# Power.net
KiCad netlist of a schematic drawn in Altium Designer
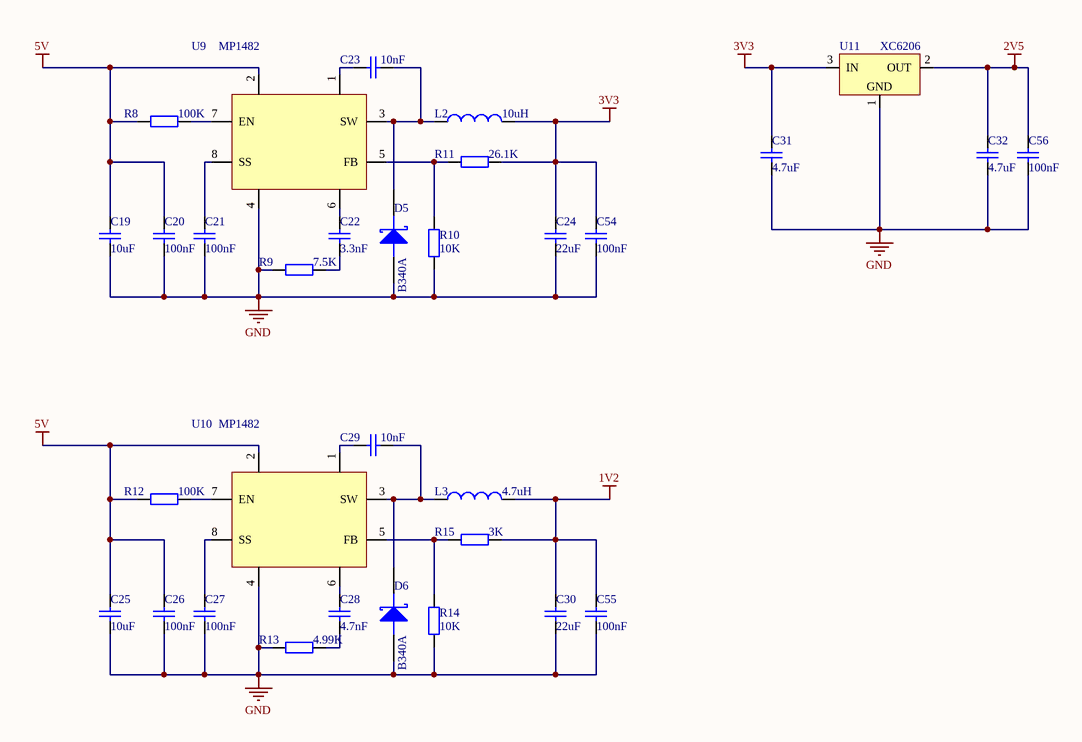
[diagram p0: Power.SchDoc]

(export (version "E")
  (design (tool "Eeschema 10.0.6"))
  (components
    (comp (ref "C19")
      (value "10uF")
      (footprint "C1206")
      (description "Capacitor")
      (fields (field (name "PUBLISHER") "Altium Limited"))
      (libsource (lib "Miscellaneous Devices") (part "Cap"))
    )
    (comp (ref "C20")
      (value "100nF")
      (footprint "C0603")
      (description "Capacitor")
      (fields (field (name "PUBLISHER") "Altium Limited"))
      (libsource (lib "Miscellaneous Devices") (part "Cap"))
    )
    (comp (ref "C21")
      (value "100nF")
      (footprint "C0603")
      (description "Capacitor")
      (fields (field (name "PUBLISHER") "Altium Limited"))
      (libsource (lib "Miscellaneous Devices") (part "Cap"))
    )
    (comp (ref "C22")
      (value "3.3nF")
      (footprint "C0603")
      (description "Capacitor")
      (fields (field (name "PUBLISHER") "Altium Limited"))
      (libsource (lib "Miscellaneous Devices") (part "Cap"))
    )
    (comp (ref "C23")
      (value "10nF")
      (footprint "C0603")
      (description "Capacitor")
      (fields (field (name "PUBLISHER") "Altium Limited"))
      (libsource (lib "Miscellaneous Devices") (part "Cap"))
    )
    (comp (ref "C24")
      (value "22uF")
      (footprint "C1206")
      (description "Capacitor")
      (fields (field (name "PUBLISHER") "Altium Limited"))
      (libsource (lib "Miscellaneous Devices") (part "Cap"))
    )
    (comp (ref "C25")
      (value "10uF")
      (footprint "C1206")
      (description "Capacitor")
      (fields (field (name "PUBLISHER") "Altium Limited"))
      (libsource (lib "Miscellaneous Devices") (part "Cap"))
    )
    (comp (ref "C26")
      (value "100nF")
      (footprint "C0603")
      (description "Capacitor")
      (fields (field (name "PUBLISHER") "Altium Limited"))
      (libsource (lib "Miscellaneous Devices") (part "Cap"))
    )
    (comp (ref "C27")
      (value "100nF")
      (footprint "C0603")
      (description "Capacitor")
      (fields (field (name "PUBLISHER") "Altium Limited"))
      (libsource (lib "Miscellaneous Devices") (part "Cap"))
    )
    (comp (ref "C28")
      (value "4.7nF")
      (footprint "C0603")
      (description "Capacitor")
      (fields (field (name "PUBLISHER") "Altium Limited"))
      (libsource (lib "Miscellaneous Devices") (part "Cap"))
    )
    (comp (ref "C29")
      (value "10nF")
      (footprint "C0603")
      (description "Capacitor")
      (fields (field (name "PUBLISHER") "Altium Limited"))
      (libsource (lib "Miscellaneous Devices") (part "Cap"))
    )
    (comp (ref "C30")
      (value "22uF")
      (footprint "C1206")
      (description "Capacitor")
      (fields (field (name "PUBLISHER") "Altium Limited"))
      (libsource (lib "Miscellaneous Devices") (part "Cap"))
    )
    (comp (ref "C31")
      (value "4.7uF")
      (footprint "C0603")
      (description "Capacitor")
      (fields (field (name "PUBLISHER") "Altium Limited"))
      (libsource (lib "Miscellaneous Devices") (part "Cap"))
    )
    (comp (ref "C32")
      (value "4.7uF")
      (footprint "C0603")
      (description "Capacitor")
      (fields (field (name "PUBLISHER") "Altium Limited"))
      (libsource (lib "Miscellaneous Devices") (part "Cap"))
    )
    (comp (ref "C54")
      (value "100nF")
      (footprint "C0603")
      (description "Capacitor")
      (fields (field (name "PUBLISHER") "Altium Limited"))
      (libsource (lib "Miscellaneous Devices") (part "Cap"))
    )
    (comp (ref "C55")
      (value "100nF")
      (footprint "C0603")
      (description "Capacitor")
      (fields (field (name "PUBLISHER") "Altium Limited"))
      (libsource (lib "Miscellaneous Devices") (part "Cap"))
    )
    (comp (ref "C56")
      (value "100nF")
      (footprint "C0603")
      (description "Capacitor")
      (fields (field (name "PUBLISHER") "Altium Limited"))
      (libsource (lib "Miscellaneous Devices") (part "Cap"))
    )
    (comp (ref "D5")
      (value "B340A")
      (footprint "SMA")
      (description "Schottky Diode")
      (libsource (lib "JL_SCH") (part "DIODE SCHOTTKY"))
    )
    (comp (ref "D6")
      (value "B340A")
      (footprint "SMA")
      (description "Schottky Diode")
      (libsource (lib "JL_SCH") (part "DIODE SCHOTTKY"))
    )
    (comp (ref "L2")
      (value "10uH")
      (footprint "CDRH5D28")
      (description "Inductor")
      (fields (field (name "PUBLISHER") "Altium Limited"))
      (libsource (lib "Miscellaneous Devices") (part "Inductor"))
    )
    (comp (ref "L3")
      (value "4.7uH")
      (footprint "CDRH5D28")
      (description "Inductor")
      (fields (field (name "PUBLISHER") "Altium Limited"))
      (libsource (lib "Miscellaneous Devices") (part "Inductor"))
    )
    (comp (ref "R8")
      (value "100K")
      (footprint "R0603")
      (description "Resistor")
      (fields (field (name "PUBLISHER") "Altium Limited"))
      (libsource (lib "Miscellaneous Devices") (part "Res2"))
    )
    (comp (ref "R9")
      (value "7.5K")
      (footprint "R0603")
      (description "Resistor")
      (fields (field (name "PUBLISHER") "Altium Limited"))
      (libsource (lib "Miscellaneous Devices") (part "Res2"))
    )
    (comp (ref "R10")
      (value "10K")
      (footprint "R0603")
      (description "Resistor")
      (fields (field (name "PUBLISHER") "Altium Limited"))
      (libsource (lib "") (part "Res2_1"))
    )
    (comp (ref "R11")
      (value "26.1K")
      (footprint "R0603")
      (description "Resistor")
      (fields (field (name "PUBLISHER") "Altium Limited"))
      (libsource (lib "Miscellaneous Devices") (part "Res2"))
    )
    (comp (ref "R12")
      (value "100K")
      (footprint "R0603")
      (description "Resistor")
      (fields (field (name "PUBLISHER") "Altium Limited"))
      (libsource (lib "Miscellaneous Devices") (part "Res2"))
    )
    (comp (ref "R13")
      (value "4.99K")
      (footprint "R0603")
      (description "Resistor")
      (fields (field (name "PUBLISHER") "Altium Limited"))
      (libsource (lib "Miscellaneous Devices") (part "Res2"))
    )
    (comp (ref "R14")
      (value "10K")
      (footprint "R0603")
      (description "Resistor")
      (fields (field (name "PUBLISHER") "Altium Limited"))
      (libsource (lib "") (part "Res2_1"))
    )
    (comp (ref "R15")
      (value "3K")
      (footprint "R0603")
      (description "Resistor")
      (fields (field (name "PUBLISHER") "Altium Limited"))
      (libsource (lib "Miscellaneous Devices") (part "Res2"))
    )
    (comp (ref "U9") (value "MP1482") (footprint "SOIC-8") (libsource (lib "ssmaster_1") (part "MP1482")))
    (comp (ref "U10") (value "MP1482") (footprint "SOIC-8") (libsource (lib "ssmaster_1") (part "MP1482")))
    (comp (ref "U11")
      (value "XC6206")
      (footprint "SOT-23")
      (description "LDO")
      (libsource (lib "ssmaster_1") (part "XC6206"))
    )
  )
  (nets
    (net (code "1") (name "1V2") (class "Default")
      (node (ref "C30") (pin "1") (pinfunction "1_1") (pintype "passive"))
      (node (ref "C55") (pin "2") (pinfunction "2_2") (pintype "passive"))
      (node (ref "L3") (pin "2") (pinfunction "2_2") (pintype "passive"))
      (node (ref "R15") (pin "1") (pinfunction "1_1") (pintype "passive"))
    )
    (net (code "2") (name "2V5") (class "Default")
      (node (ref "C32") (pin "2") (pinfunction "2_2") (pintype "passive"))
      (node (ref "C56") (pin "2") (pinfunction "2_2") (pintype "passive"))
      (node (ref "U11") (pin "2") (pinfunction "OUT_2") (pintype "power_in"))
    )
    (net (code "3") (name "3V3") (class "Default")
      (node (ref "C24") (pin "1") (pinfunction "1_1") (pintype "passive"))
      (node (ref "C31") (pin "2") (pinfunction "2_2") (pintype "passive"))
      (node (ref "C54") (pin "2") (pinfunction "2_2") (pintype "passive"))
      (node (ref "L2") (pin "2") (pinfunction "2_2") (pintype "passive"))
      (node (ref "R11") (pin "1") (pinfunction "1_1") (pintype "passive"))
      (node (ref "U11") (pin "3") (pinfunction "IN_3") (pintype "power_in"))
    )
    (net (code "4") (name "5V") (class "Default")
      (node (ref "C19") (pin "2") (pinfunction "2_2") (pintype "passive"))
      (node (ref "C20") (pin "2") (pinfunction "2_2") (pintype "passive"))
      (node (ref "C25") (pin "2") (pinfunction "2_2") (pintype "passive"))
      (node (ref "C26") (pin "2") (pinfunction "2_2") (pintype "passive"))
      (node (ref "R12") (pin "2") (pinfunction "2_2") (pintype "passive"))
      (node (ref "R8") (pin "2") (pinfunction "2_2") (pintype "passive"))
      (node (ref "U10") (pin "2") (pinfunction "IN_2") (pintype "power_in"))
      (node (ref "U9") (pin "2") (pinfunction "IN_2") (pintype "power_in"))
    )
    (net (code "5") (name "GND") (class "Default")
      (node (ref "C19") (pin "1") (pinfunction "1_1") (pintype "passive"))
      (node (ref "C20") (pin "1") (pinfunction "1_1") (pintype "passive"))
      (node (ref "C21") (pin "1") (pinfunction "1_1") (pintype "passive"))
      (node (ref "C24") (pin "2") (pinfunction "2_2") (pintype "passive"))
      (node (ref "C25") (pin "1") (pinfunction "1_1") (pintype "passive"))
      (node (ref "C26") (pin "1") (pinfunction "1_1") (pintype "passive"))
      (node (ref "C27") (pin "1") (pinfunction "1_1") (pintype "passive"))
      (node (ref "C30") (pin "2") (pinfunction "2_2") (pintype "passive"))
      (node (ref "C31") (pin "1") (pinfunction "1_1") (pintype "passive"))
      (node (ref "C32") (pin "1") (pinfunction "1_1") (pintype "passive"))
      (node (ref "C54") (pin "1") (pinfunction "1_1") (pintype "passive"))
      (node (ref "C55") (pin "1") (pinfunction "1_1") (pintype "passive"))
      (node (ref "C56") (pin "1") (pinfunction "1_1") (pintype "passive"))
      (node (ref "D5") (pin "1") (pinfunction "A_1") (pintype "passive"))
      (node (ref "D6") (pin "1") (pinfunction "A_1") (pintype "passive"))
      (node (ref "R10") (pin "1") (pinfunction "1_1") (pintype "passive"))
      (node (ref "R13") (pin "2") (pinfunction "2_2") (pintype "passive"))
      (node (ref "R14") (pin "1") (pinfunction "1_1") (pintype "passive"))
      (node (ref "R9") (pin "2") (pinfunction "2_2") (pintype "passive"))
      (node (ref "U10") (pin "4") (pinfunction "GND_4") (pintype "power_in"))
      (node (ref "U11") (pin "1") (pinfunction "GND_1") (pintype "power_in"))
      (node (ref "U9") (pin "4") (pinfunction "GND_4") (pintype "power_in"))
    )
    (net (code "6") (name "Net-(C22-Pad1)") (class "Default")
      (node (ref "C22") (pin "1") (pinfunction "1_1") (pintype "passive"))
      (node (ref "R9") (pin "1") (pinfunction "1_1") (pintype "passive"))
    )
    (net (code "7") (name "Net-(C28-Pad1)") (class "Default")
      (node (ref "C28") (pin "1") (pinfunction "1_1") (pintype "passive"))
      (node (ref "R13") (pin "1") (pinfunction "1_1") (pintype "passive"))
    )
    (net (code "8") (name "Net-(D5-K)") (class "Default")
      (node (ref "C23") (pin "1") (pinfunction "1_1") (pintype "passive"))
      (node (ref "D5") (pin "2") (pinfunction "K_2") (pintype "passive"))
      (node (ref "L2") (pin "1") (pinfunction "1_1") (pintype "passive"))
      (node (ref "U9") (pin "3") (pinfunction "SW_3") (pintype "passive"))
    )
    (net (code "9") (name "Net-(D6-K)") (class "Default")
      (node (ref "C29") (pin "1") (pinfunction "1_1") (pintype "passive"))
      (node (ref "D6") (pin "2") (pinfunction "K_2") (pintype "passive"))
      (node (ref "L3") (pin "1") (pinfunction "1_1") (pintype "passive"))
      (node (ref "U10") (pin "3") (pinfunction "SW_3") (pintype "passive"))
    )
    (net (code "10") (name "Net-(U9-BS)") (class "Default")
      (node (ref "C23") (pin "2") (pinfunction "2_2") (pintype "passive"))
      (node (ref "U9") (pin "1") (pinfunction "BS_1") (pintype "passive"))
    )
    (net (code "11") (name "Net-(U9-COMP)") (class "Default")
      (node (ref "C22") (pin "2") (pinfunction "2_2") (pintype "passive"))
      (node (ref "U9") (pin "6") (pinfunction "COMP_6") (pintype "passive"))
    )
    (net (code "12") (name "Net-(U9-EN)") (class "Default")
      (node (ref "R8") (pin "1") (pinfunction "1_1") (pintype "passive"))
      (node (ref "U9") (pin "7") (pinfunction "EN_7") (pintype "passive"))
    )
    (net (code "13") (name "Net-(U9-FB)") (class "Default")
      (node (ref "R10") (pin "2") (pinfunction "2_2") (pintype "passive"))
      (node (ref "R11") (pin "2") (pinfunction "2_2") (pintype "passive"))
      (node (ref "U9") (pin "5") (pinfunction "FB_5") (pintype "passive"))
    )
    (net (code "14") (name "Net-(U9-SS)") (class "Default")
      (node (ref "C21") (pin "2") (pinfunction "2_2") (pintype "passive"))
      (node (ref "U9") (pin "8") (pinfunction "SS_8") (pintype "passive"))
    )
    (net (code "15") (name "Net-(U10-BS)") (class "Default")
      (node (ref "C29") (pin "2") (pinfunction "2_2") (pintype "passive"))
      (node (ref "U10") (pin "1") (pinfunction "BS_1") (pintype "passive"))
    )
    (net (code "16") (name "Net-(U10-COMP)") (class "Default")
      (node (ref "C28") (pin "2") (pinfunction "2_2") (pintype "passive"))
      (node (ref "U10") (pin "6") (pinfunction "COMP_6") (pintype "passive"))
    )
    (net (code "17") (name "Net-(U10-EN)") (class "Default")
      (node (ref "R12") (pin "1") (pinfunction "1_1") (pintype "passive"))
      (node (ref "U10") (pin "7") (pinfunction "EN_7") (pintype "passive"))
    )
    (net (code "18") (name "Net-(U10-FB)") (class "Default")
      (node (ref "R14") (pin "2") (pinfunction "2_2") (pintype "passive"))
      (node (ref "R15") (pin "2") (pinfunction "2_2") (pintype "passive"))
      (node (ref "U10") (pin "5") (pinfunction "FB_5") (pintype "passive"))
    )
    (net (code "19") (name "Net-(U10-SS)") (class "Default")
      (node (ref "C27") (pin "2") (pinfunction "2_2") (pintype "passive"))
      (node (ref "U10") (pin "8") (pinfunction "SS_8") (pintype "passive"))
    )
  )
)
